# Blinky.net
KiCad netlist of a schematic drawn in EAGLE
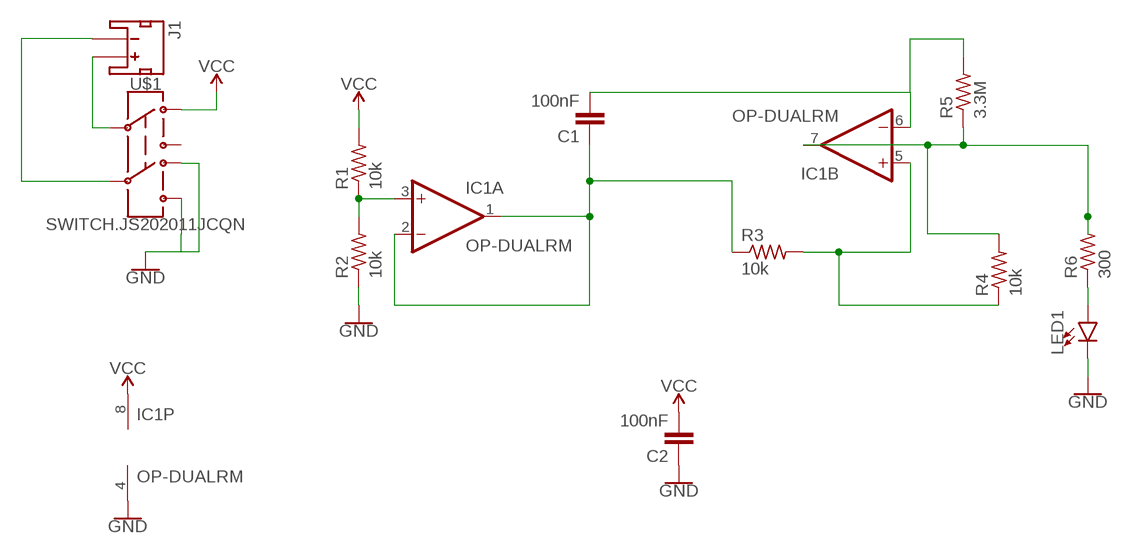
[diagram p0: schematic, sheet 1]

(export (version "E")
  (design (tool "Eeschema 10.0.6"))
  (components
    (comp (ref "C1")
      (value "100nF")
      (footprint "eagle-import:C0402")
      (libsource (lib "eagle-import") (part "CAPACITOR0402"))
    )
    (comp (ref "C2")
      (value "100nF")
      (footprint "eagle-import:C0402")
      (libsource (lib "eagle-import") (part "CAPACITOR0402"))
    )
    (comp (ref "IC1")
      (value "OP-DUALRM")
      (footprint "eagle-import:MSOP08")
      (fields (field (name "MF") "ALTERA CORPORATION") (field (name "MPN") "AD8607ARMZ-REEL"))
      (libsource (lib "eagle-import") (part "OP-DUALRM"))
    )
    (comp (ref "J1")
      (value "JST_2MM_MALE")
      (footprint "eagle-import:JST-2-SMD")
      (libsource (lib "eagle-import") (part "JST_2MM_MALE"))
    )
    (comp (ref "LED1")
      (value "LED0603")
      (footprint "eagle-import:LED-0603")
      (libsource (lib "eagle-import") (part "LED0603"))
    )
    (comp (ref "R1")
      (value "10k")
      (footprint "eagle-import:R0402")
      (libsource (lib "eagle-import") (part "RESISTOR0402"))
    )
    (comp (ref "R2")
      (value "10k")
      (footprint "eagle-import:R0402")
      (libsource (lib "eagle-import") (part "RESISTOR0402"))
    )
    (comp (ref "R3")
      (value "10k")
      (footprint "eagle-import:R0402")
      (libsource (lib "eagle-import") (part "RESISTOR0402"))
    )
    (comp (ref "R4")
      (value "10k")
      (footprint "eagle-import:R0402")
      (libsource (lib "eagle-import") (part "RESISTOR0402"))
    )
    (comp (ref "R5")
      (value "3.3M")
      (footprint "eagle-import:R0402")
      (libsource (lib "eagle-import") (part "RESISTOR0402"))
    )
    (comp (ref "R6")
      (value "300")
      (footprint "eagle-import:R0402")
      (libsource (lib "eagle-import") (part "RESISTOR0402"))
    )
    (comp (ref "U$1")
      (value "SWITCH.JS202011JCQN")
      (footprint "eagle-import:SWITCH.00")
      (libsource (lib "eagle-import") (part "SWITCH.JS202011JCQN"))
    )
  )
  (nets
    (net (code "1") (name "GND") (class "Default")
      (node (ref "C2") (pin "1") (pinfunction "1_1") (pintype "passive"))
      (node (ref "IC1") (pin "4") (pinfunction "V-_4") (pintype "power_in"))
      (node (ref "LED1") (pin "C") (pinfunction "C_C") (pintype "passive"))
      (node (ref "R2") (pin "1") (pinfunction "1_1") (pintype "passive"))
      (node (ref "U$1") (pin "5") (pinfunction "5_5") (pintype "bidirectional"))
      (node (ref "U$1") (pin "7") (pinfunction "7_7") (pintype "bidirectional"))
    )
    (net (code "2") (name "Net-(IC1A-+IN)") (class "Default")
      (node (ref "IC1") (pin "3") (pinfunction "+IN_3") (pintype "input"))
      (node (ref "R1") (pin "1") (pinfunction "1_1") (pintype "passive"))
      (node (ref "R2") (pin "2") (pinfunction "2_2") (pintype "passive"))
    )
    (net (code "3") (name "Net-(IC1A--IN)") (class "Default")
      (node (ref "C1") (pin "1") (pinfunction "1_1") (pintype "passive"))
      (node (ref "IC1") (pin "1") (pinfunction "OUT_1") (pintype "output"))
      (node (ref "IC1") (pin "2") (pinfunction "-IN_2") (pintype "input"))
      (node (ref "R3") (pin "1") (pinfunction "1_1") (pintype "passive"))
    )
    (net (code "4") (name "Net-(IC1B-+IN)") (class "Default")
      (node (ref "IC1") (pin "5") (pinfunction "+IN_5") (pintype "input"))
      (node (ref "R3") (pin "2") (pinfunction "2_2") (pintype "passive"))
      (node (ref "R4") (pin "1") (pinfunction "1_1") (pintype "passive"))
    )
    (net (code "5") (name "Net-(IC1B--IN)") (class "Default")
      (node (ref "C1") (pin "2") (pinfunction "2_2") (pintype "passive"))
      (node (ref "IC1") (pin "6") (pinfunction "-IN_6") (pintype "input"))
      (node (ref "R5") (pin "2") (pinfunction "2_2") (pintype "passive"))
    )
    (net (code "6") (name "Net-(IC1B-OUT)") (class "Default")
      (node (ref "IC1") (pin "7") (pinfunction "OUT_7") (pintype "output"))
      (node (ref "R4") (pin "2") (pinfunction "2_2") (pintype "passive"))
      (node (ref "R5") (pin "1") (pinfunction "1_1") (pintype "passive"))
      (node (ref "R6") (pin "2") (pinfunction "2_2") (pintype "passive"))
    )
    (net (code "7") (name "Net-(J1-+)") (class "Default")
      (node (ref "J1") (pin "2") (pinfunction "+_2") (pintype "bidirectional"))
      (node (ref "U$1") (pin "2") (pinfunction "2_2") (pintype "bidirectional"))
    )
    (net (code "8") (name "Net-(J1--)") (class "Default")
      (node (ref "J1") (pin "1") (pinfunction "-_1") (pintype "bidirectional"))
      (node (ref "U$1") (pin "6") (pinfunction "6_6") (pintype "bidirectional"))
    )
    (net (code "9") (name "Net-(LED1-PadA)") (class "Default")
      (node (ref "LED1") (pin "A") (pinfunction "A_A") (pintype "passive"))
      (node (ref "R6") (pin "1") (pinfunction "1_1") (pintype "passive"))
    )
    (net (code "10") (name "VCC") (class "Default")
      (node (ref "C2") (pin "2") (pinfunction "2_2") (pintype "passive"))
      (node (ref "IC1") (pin "8") (pinfunction "V+_8") (pintype "power_in"))
      (node (ref "R1") (pin "2") (pinfunction "2_2") (pintype "passive"))
      (node (ref "U$1") (pin "1") (pinfunction "1_1") (pintype "bidirectional"))
    )
    (net (code "11") (name "unconnected-(J1-PAD1-PadNC1)") (class "Default")
      (node (ref "J1") (pin "NC1") (pinfunction "PAD1_NC1") (pintype "bidirectional"))
    )
    (net (code "12") (name "unconnected-(J1-PAD2-PadNC2)") (class "Default")
      (node (ref "J1") (pin "NC2") (pinfunction "PAD2_NC2") (pintype "bidirectional"))
    )
    (net (code "13") (name "unconnected-(U$1-Pad3)") (class "Default")
      (node (ref "U$1") (pin "3") (pinfunction "3_3") (pintype "bidirectional"))
    )
  )
)
